# test.net
KiCad netlist of a schematic drawn in Altium Designer
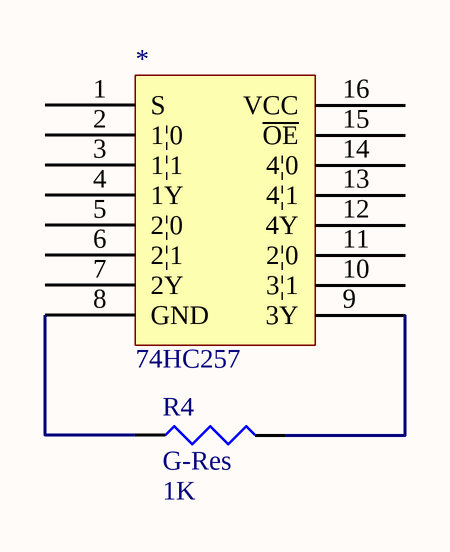
[diagram p0: test.SchDoc]

(export (version "E")
  (design (tool "Eeschema 10.0.6"))
  (components
    (comp (ref "*")
      (value "74HC257")
      (footprint "DIP16_LGE1.0")
      (libsource (lib "controllerSchLib") (part "74HC257"))
    )
    (comp (ref "R4")
      (value "G-Res")
      (footprint "Res10mm_LGE1.0")
      (description "resistor (specify value)")
      (fields (field (name "ALTIUM_VALUE") "1K") (field (name "PUBLISHER") "Altium Limited"))
      (libsource (lib "PartsDatabaseV13p1") (part "G-Res"))
    )
  )
  (nets
    (net (code "1") (name "Net-(*-3Y)") (class "Default")
      (node (ref "*") (pin "9") (pinfunction "3Y_9") (pintype "passive"))
      (node (ref "R4") (pin "2") (pinfunction "2_2") (pintype "passive"))
    )
    (net (code "2") (name "Net-(*-GND)") (class "Default")
      (node (ref "*") (pin "8") (pinfunction "GND_8") (pintype "passive"))
      (node (ref "R4") (pin "1") (pinfunction "1_1") (pintype "passive"))
    )
    (net (code "3") (name "unconnected-(*-1Y-Pad4)") (class "Default")
      (node (ref "*") (pin "4") (pinfunction "1Y_4") (pintype "passive"))
    )
    (net (code "4") (name "unconnected-(*-1¦0-Pad2)") (class "Default")
      (node (ref "*") (pin "2") (pinfunction "1¦0_2") (pintype "passive"))
    )
    (net (code "5") (name "unconnected-(*-1¦1-Pad3)") (class "Default")
      (node (ref "*") (pin "3") (pinfunction "1¦1_3") (pintype "passive"))
    )
    (net (code "6") (name "unconnected-(*-2Y-Pad7)") (class "Default")
      (node (ref "*") (pin "7") (pinfunction "2Y_7") (pintype "passive"))
    )
    (net (code "7") (name "unconnected-(*-2¦0-Pad5)") (class "Default")
      (node (ref "*") (pin "5") (pinfunction "2¦0_5") (pintype "passive"))
    )
    (net (code "8") (name "unconnected-(*-2¦0-Pad11)") (class "Default")
      (node (ref "*") (pin "11") (pinfunction "2¦0_11") (pintype "passive"))
    )
    (net (code "9") (name "unconnected-(*-2¦1-Pad6)") (class "Default")
      (node (ref "*") (pin "6") (pinfunction "2¦1_6") (pintype "passive"))
    )
    (net (code "10") (name "unconnected-(*-3¦1-Pad10)") (class "Default")
      (node (ref "*") (pin "10") (pinfunction "3¦1_10") (pintype "passive"))
    )
    (net (code "11") (name "unconnected-(*-4Y-Pad12)") (class "Default")
      (node (ref "*") (pin "12") (pinfunction "4Y_12") (pintype "passive"))
    )
    (net (code "12") (name "unconnected-(*-4¦0-Pad14)") (class "Default")
      (node (ref "*") (pin "14") (pinfunction "4¦0_14") (pintype "passive"))
    )
    (net (code "13") (name "unconnected-(*-4¦1-Pad13)") (class "Default")
      (node (ref "*") (pin "13") (pinfunction "4¦1_13") (pintype "passive"))
    )
    (net (code "14") (name "unconnected-(*-S-Pad1)") (class "Default")
      (node (ref "*") (pin "1") (pinfunction "S_1") (pintype "passive"))
    )
    (net (code "15") (name "unconnected-(*-VCC-Pad16)") (class "Default")
      (node (ref "*") (pin "16") (pinfunction "VCC_16") (pintype "passive"))
    )
    (net (code "16") (name "unconnected-(*-~{OE}-Pad15)") (class "Default")
      (node (ref "*") (pin "15") (pinfunction "~{OE}_15") (pintype "passive"))
    )
  )
)
